# TPS5420_SMPS.net
KiCad netlist of a schematic drawn in Altium Designer
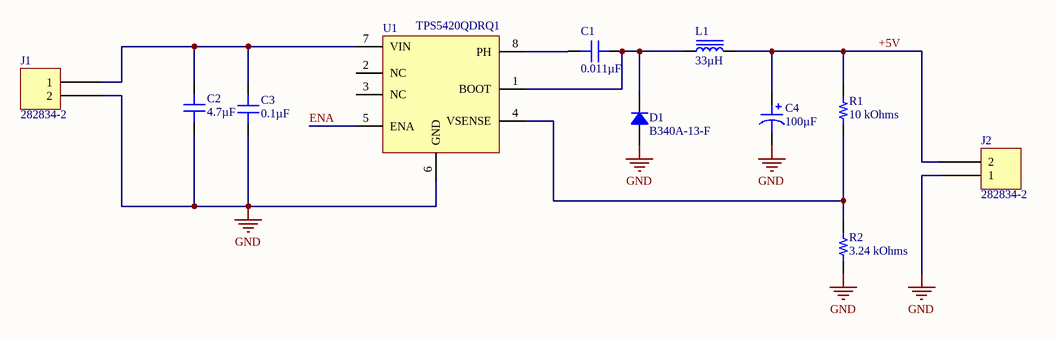
[diagram p0: TPS5420_SMPS.SchDoc]

(export (version "E")
  (design (tool "Eeschema 10.0.6"))
  (components
    (comp (ref "C1")
      (value "0.011µF")
      (footprint "CAP 0805_2012")
      (description "CAP CER 0.011UF 50V C0G/NP0 0805")
      (fields
        (field (name "PART NUMBER") "GRM2195C1H113JA01D")
        (field (name "MANUFACTURER") "Murata Electronics")
      )
      (libsource (lib "Celestial Altium Library - altium_library") (part "Capacitor"))
    )
    (comp (ref "C2")
      (value "4.7µF")
      (footprint "CAP 0805_2012")
      (description "CAP CER 4.7UF 35V X5R 0805")
      (fields
        (field (name "PART NUMBER") "C2012X5R1V475K125AC")
        (field (name "MANUFACTURER") "TDK Corporation")
      )
      (libsource (lib "Celestial Altium Library - altium_library") (part "Capacitor"))
    )
    (comp (ref "C3")
      (value "0.1µF")
      (footprint "CAP 0805_2012")
      (description "CAP CER 0.1UF 50V X7R 0805")
      (fields (field (name "PART NUMBER") "C0805C104M5RACAUTO") (field (name "MANUFACTURER") "KEMET"))
      (libsource (lib "Celestial Altium Library - altium_library") (part "Capacitor"))
    )
    (comp (ref "C4")
      (value "100µF")
      (footprint "CAP ALSMD 6.6MM H6.1MM")
      (description "CAP ALUM 100UF 20% 16V SMD")
      (fields (field (name "PART NUMBER") "107SML016M") (field (name "MANUFACTURER") "Illinois Capacitor"))
      (libsource (lib "Celestial Altium Library - altium_library") (part "Polarised Capacitor"))
    )
    (comp (ref "D1")
      (value "B340A-13-F")
      (footprint "DO214AC SMA")
      (description "DIODE SCHOTTKY 40V 3A SMA")
      (fields (field (name "MANUFACTURER") "Diodes Incorporated"))
      (libsource (lib "Celestial Altium Library - altium_library") (part "Diode"))
    )
    (comp (ref "J1")
      (value "282834-2")
      (footprint "TE 282834-2")
      (description "TERM BLK 2P SIDE ENT 2.54MM PCB")
      (fields (field (name "MANUFACTURER") "TE Connectivity AMP Connectors") (field (name "VOLTAGE") "150V"))
      (libsource (lib "Celestial Altium Library - altium_library") (part "2 Pin"))
    )
    (comp (ref "J2")
      (value "282834-2")
      (footprint "TE 282834-2")
      (description "TERM BLK 2P SIDE ENT 2.54MM PCB")
      (fields (field (name "MANUFACTURER") "TE Connectivity AMP Connectors") (field (name "VOLTAGE") "150V"))
      (libsource (lib "") (part "2 Pin_1"))
    )
    (comp (ref "L1")
      (value "33µH")
      (footprint "BOURNS SRN8040")
      (description "FIXED IND 33UH 1.7A 145 MOHM SMD")
      (fields (field (name "PART NUMBER") "SRN8040-330M") (field (name "MANUFACTURER") "Bourns Inc."))
      (libsource (lib "Celestial Altium Library - altium_library") (part "Inductor"))
    )
    (comp (ref "R1")
      (value "10 kOhms")
      (footprint "RES 0805_2012")
      (description "RES 10K OHM 0.1% 1/8W 0805")
      (fields
        (field (name "PART NUMBER") "ERA-6AEB103V")
        (field (name "MANUFACTURER") "Panasonic Electronic Components")
      )
      (libsource (lib "Celestial Altium Library - altium_library") (part "Resistor"))
    )
    (comp (ref "R2")
      (value "3.24 kOhms")
      (footprint "RES 0805_2012")
      (description "RES 3.24K OHM 0.1% 1/8W 0805")
      (fields (field (name "PART NUMBER") "TNPW08053K24BEEA") (field (name "MANUFACTURER") "Vishay Dale"))
      (libsource (lib "Celestial Altium Library - altium_library") (part "Resistor"))
    )
    (comp (ref "U1")
      (value "TPS5420QDRQ1")
      (footprint "SO8")
      (description "IC REG BUCK ADJUSTABLE 2A 8SOIC")
      (fields
        (field (name "MANUFACTURER") "Texas Instruments")
        (field (name "DIGI-KEY PART NUMBER") "296-23226-6-ND")
        (field (name "MANUFACTURER PRODUCT NUMBER") "TPS5420QDRQ1")
      )
      (libsource (lib "TPS5420QDRQ1") (part "TPS5420QDRQ1"))
    )
  )
  (nets
    (net (code "1") (name "/+5V") (class "Default")
      (node (ref "C4") (pin "1") (pinfunction "1_1") (pintype "passive"))
      (node (ref "J2") (pin "2") (pinfunction "2_2") (pintype "passive"))
      (node (ref "L1") (pin "2") (pinfunction "2_2") (pintype "passive"))
      (node (ref "R1") (pin "2") (pinfunction "2_2") (pintype "passive"))
    )
    (net (code "2") (name "/ENA") (class "Default")
      (node (ref "U1") (pin "5") (pinfunction "ENA_5") (pintype "passive"))
    )
    (net (code "3") (name "GND") (class "Default")
      (node (ref "C2") (pin "1") (pinfunction "1_1") (pintype "passive"))
      (node (ref "C3") (pin "1") (pinfunction "1_1") (pintype "passive"))
      (node (ref "C4") (pin "2") (pinfunction "2_2") (pintype "passive"))
      (node (ref "D1") (pin "1") (pinfunction "1_1") (pintype "passive"))
      (node (ref "J1") (pin "2") (pinfunction "2_2") (pintype "passive"))
      (node (ref "J2") (pin "1") (pinfunction "1_1") (pintype "passive"))
      (node (ref "R2") (pin "1") (pinfunction "1_1") (pintype "passive"))
      (node (ref "U1") (pin "6") (pinfunction "GND_6") (pintype "passive"))
    )
    (net (code "4") (name "Net-(U1-BOOT)") (class "Default")
      (node (ref "C1") (pin "2") (pinfunction "2_2") (pintype "passive"))
      (node (ref "D1") (pin "2") (pinfunction "2_2") (pintype "passive"))
      (node (ref "L1") (pin "1") (pinfunction "1_1") (pintype "passive"))
      (node (ref "U1") (pin "1") (pinfunction "BOOT_1") (pintype "passive"))
    )
    (net (code "5") (name "Net-(U1-PH)") (class "Default")
      (node (ref "C1") (pin "1") (pinfunction "1_1") (pintype "passive"))
      (node (ref "U1") (pin "8") (pinfunction "PH_8") (pintype "passive"))
    )
    (net (code "6") (name "Net-(U1-VIN)") (class "Default")
      (node (ref "C2") (pin "2") (pinfunction "2_2") (pintype "passive"))
      (node (ref "C3") (pin "2") (pinfunction "2_2") (pintype "passive"))
      (node (ref "J1") (pin "1") (pinfunction "1_1") (pintype "passive"))
      (node (ref "U1") (pin "7") (pinfunction "VIN_7") (pintype "passive"))
    )
    (net (code "7") (name "Net-(U1-VSENSE)") (class "Default")
      (node (ref "R1") (pin "1") (pinfunction "1_1") (pintype "passive"))
      (node (ref "R2") (pin "2") (pinfunction "2_2") (pintype "passive"))
      (node (ref "U1") (pin "4") (pinfunction "VSENSE_4") (pintype "passive"))
    )
    (net (code "8") (name "unconnected-(U1-NC-Pad2)") (class "Default")
      (node (ref "U1") (pin "2") (pinfunction "NC_2") (pintype "passive"))
    )
    (net (code "9") (name "unconnected-(U1-NC-Pad3)") (class "Default")
      (node (ref "U1") (pin "3") (pinfunction "NC_3") (pintype "passive"))
    )
  )
)
